# sym-var4.net
KiCad netlist of a schematic drawn in EAGLE
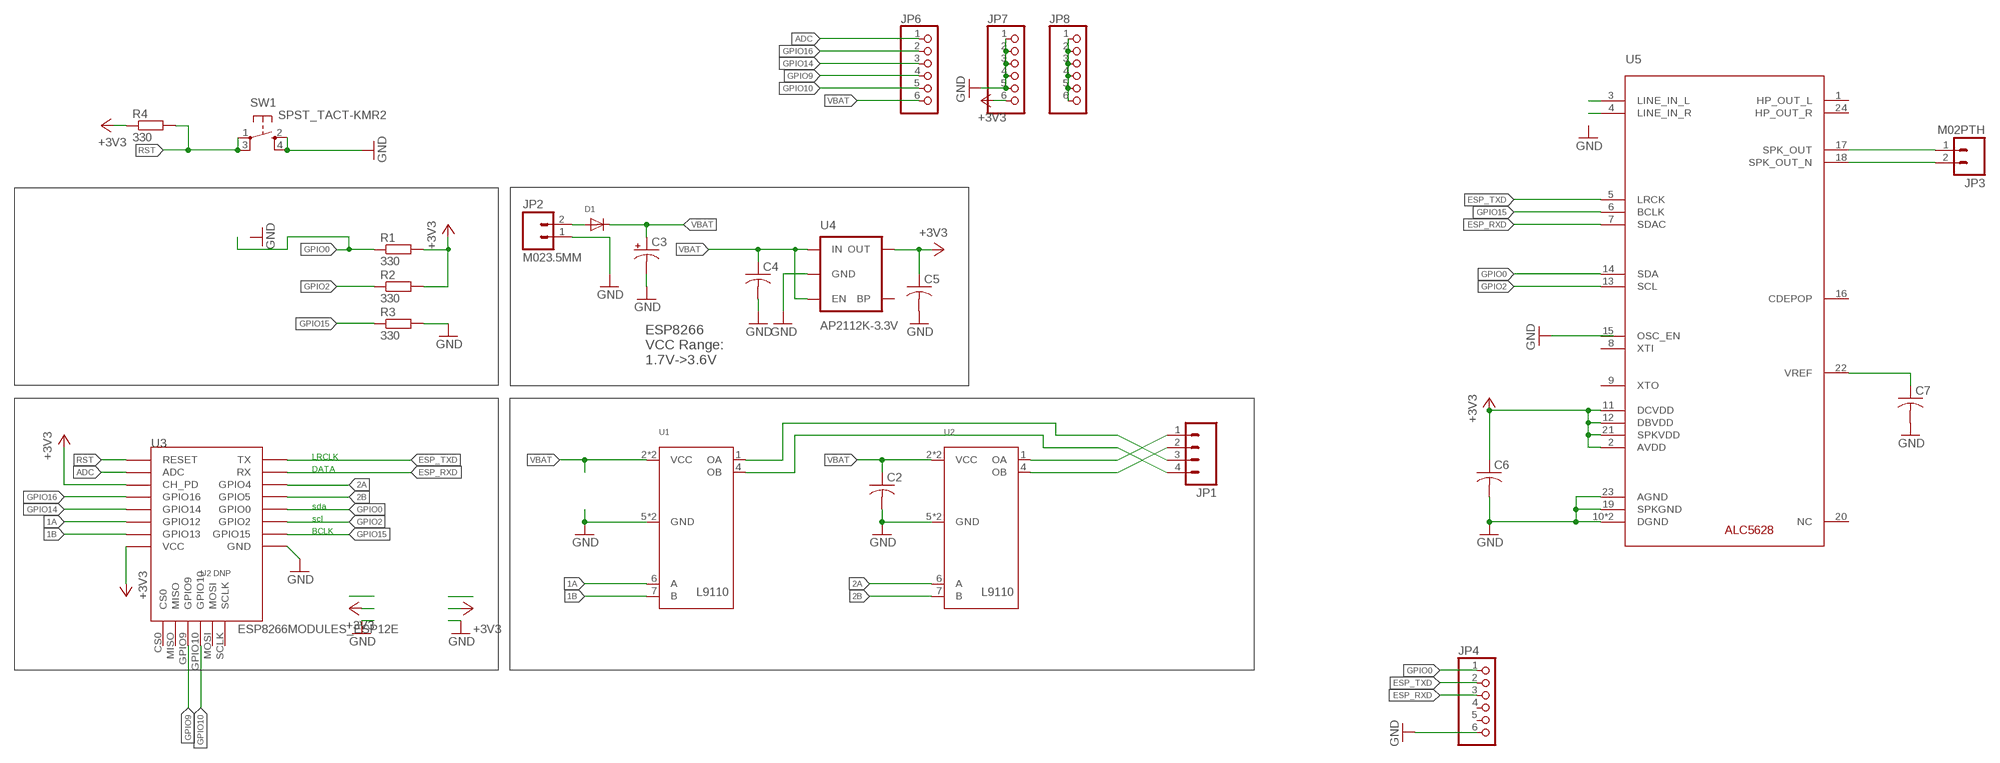
[diagram p0: schematic, sheet 1]

(export (version "E")
  (design (tool "Eeschema 10.0.6"))
  (components
    (comp (ref "C2")
      (value "C-USC0805")
      (footprint "eagle-import:C0805")
      (libsource (lib "eagle-import") (part "C-USC0805"))
    )
    (comp (ref "C3")
      (value "CPOL-USE2-5")
      (footprint "eagle-import:E2-5")
      (libsource (lib "eagle-import") (part "CPOL-USE2-5"))
    )
    (comp (ref "C4")
      (value "C-USC0805")
      (footprint "eagle-import:C0805")
      (libsource (lib "eagle-import") (part "C-USC0805"))
    )
    (comp (ref "C5")
      (value "C-USC0805")
      (footprint "eagle-import:C0805")
      (libsource (lib "eagle-import") (part "C-USC0805"))
    )
    (comp (ref "C6")
      (value "C-USC0805")
      (footprint "eagle-import:C0805")
      (libsource (lib "eagle-import") (part "C-USC0805"))
    )
    (comp (ref "C7")
      (value "C-USC0805")
      (footprint "eagle-import:C0805")
      (libsource (lib "eagle-import") (part "C-USC0805"))
    )
    (comp (ref "D1")
      (value "DIODESMA")
      (footprint "eagle-import:SMADIODE")
      (libsource (lib "eagle-import") (part "DIODESMA"))
    )
    (comp (ref "JP1")
      (value "M04SCREW")
      (footprint "eagle-import:SCREWTERMINAL-3.5MM-4")
      (libsource (lib "eagle-import") (part "M04SCREW"))
    )
    (comp (ref "JP2")
      (value "M023.5MM")
      (footprint "eagle-import:SCREWTERMINAL-3.5MM-2")
      (libsource (lib "eagle-import") (part "M023.5MM"))
    )
    (comp (ref "JP3")
      (value "M02PTH")
      (footprint "eagle-import:1X02")
      (libsource (lib "eagle-import") (part "M02PTH"))
    )
    (comp (ref "JP4")
      (value "PINHD-1X6")
      (footprint "eagle-import:1X06")
      (libsource (lib "eagle-import") (part "PINHD-1X6"))
    )
    (comp (ref "JP6")
      (value "PINHD-1X6")
      (footprint "eagle-import:1X06")
      (libsource (lib "eagle-import") (part "PINHD-1X6"))
    )
    (comp (ref "JP7")
      (value "PINHD-1X6")
      (footprint "eagle-import:1X06")
      (libsource (lib "eagle-import") (part "PINHD-1X6"))
    )
    (comp (ref "JP8")
      (value "PINHD-1X6")
      (footprint "eagle-import:1X06")
      (libsource (lib "eagle-import") (part "PINHD-1X6"))
    )
    (comp (ref "R1")
      (value "330")
      (footprint "eagle-import:R0805")
      (libsource (lib "eagle-import") (part "R-EU_R0805"))
    )
    (comp (ref "R2")
      (value "330")
      (footprint "eagle-import:R0805")
      (libsource (lib "eagle-import") (part "R-EU_R0805"))
    )
    (comp (ref "R3")
      (value "330")
      (footprint "eagle-import:R0805")
      (libsource (lib "eagle-import") (part "R-EU_R0805"))
    )
    (comp (ref "R4")
      (value "330")
      (footprint "eagle-import:R0805")
      (libsource (lib "eagle-import") (part "R-EU_R0805"))
    )
    (comp (ref "SW1")
      (value "SPST_TACT-KMR2")
      (footprint "eagle-import:KMR2")
      (libsource (lib "eagle-import") (part "SPST_TACT-KMR2"))
    )
    (comp (ref "U1")
      (value "L9110")
      (footprint "eagle-import:DIP8")
      (libsource (lib "eagle-import") (part "L9110"))
    )
    (comp (ref "U2")
      (value "L9110")
      (footprint "eagle-import:DIP8")
      (libsource (lib "eagle-import") (part "L9110"))
    )
    (comp (ref "U3")
      (value "ESP8266MODULES_ESP12E")
      (footprint "eagle-import:ESP8266MODULES_ESP12E")
      (libsource (lib "eagle-import") (part "ESP8266MODULES_ESP12E"))
    )
    (comp (ref "U4")
      (value "AP2112K-3.3V")
      (footprint "eagle-import:SOT23-5")
      (libsource (lib "eagle-import") (part "V_REG_LDOSMD"))
    )
    (comp (ref "U5")
      (value "ALC5628")
      (footprint "eagle-import:QFN24")
      (libsource (lib "eagle-import") (part "ALC5628"))
    )
  )
  (nets
    (net (code "1") (name "+3V3") (class "Default")
      (node (ref "C5") (pin "1") (pinfunction "1_1") (pintype "passive"))
      (node (ref "C6") (pin "1") (pinfunction "1_1") (pintype "passive"))
      (node (ref "JP7") (pin "6") (pinfunction "6_6") (pintype "passive"))
      (node (ref "R1") (pin "2") (pinfunction "2_2") (pintype "passive"))
      (node (ref "R2") (pin "2") (pinfunction "2_2") (pintype "passive"))
      (node (ref "R4") (pin "1") (pinfunction "1_1") (pintype "passive"))
      (node (ref "U3") (pin "CH_PD") (pinfunction "CH_PD_CH_PD") (pintype "bidirectional"))
      (node (ref "U3") (pin "VCC") (pinfunction "VCC_VCC") (pintype "bidirectional"))
      (node (ref "U4") (pin "5") (pinfunction "OUT_5") (pintype "passive"))
      (node (ref "U5") (pin "11") (pinfunction "DCVDD_11") (pintype "bidirectional"))
      (node (ref "U5") (pin "12") (pinfunction "DBVDD_12") (pintype "bidirectional"))
      (node (ref "U5") (pin "2") (pinfunction "AVDD_2") (pintype "bidirectional"))
      (node (ref "U5") (pin "21") (pinfunction "SPKVDD_21") (pintype "bidirectional"))
    )
    (net (code "2") (name "1A") (class "Default")
      (node (ref "U1") (pin "6") (pinfunction "A_6") (pintype "bidirectional"))
      (node (ref "U3") (pin "GPIO12") (pinfunction "GPIO12_GPIO12") (pintype "bidirectional"))
    )
    (net (code "3") (name "1B") (class "Default")
      (node (ref "U1") (pin "7") (pinfunction "B_7") (pintype "bidirectional"))
      (node (ref "U3") (pin "GPIO_13") (pinfunction "GPIO13_GPIO_13") (pintype "bidirectional"))
    )
    (net (code "4") (name "2A") (class "Default")
      (node (ref "U2") (pin "6") (pinfunction "A_6") (pintype "bidirectional"))
      (node (ref "U3") (pin "GPIO4") (pinfunction "GPIO4_GPIO4") (pintype "bidirectional"))
    )
    (net (code "5") (name "2B") (class "Default")
      (node (ref "U2") (pin "7") (pinfunction "B_7") (pintype "bidirectional"))
      (node (ref "U3") (pin "GPIO5") (pinfunction "GPIO5_GPIO5") (pintype "bidirectional"))
    )
    (net (code "6") (name "ADC") (class "Default")
      (node (ref "JP6") (pin "1") (pinfunction "1_1") (pintype "passive"))
      (node (ref "U3") (pin "ADC") (pinfunction "ADC_ADC") (pintype "bidirectional"))
    )
    (net (code "7") (name "ESP_RXD") (class "Default")
      (node (ref "JP4") (pin "3") (pinfunction "3_3") (pintype "passive"))
      (node (ref "U3") (pin "RX") (pinfunction "RX_RX") (pintype "bidirectional"))
      (node (ref "U5") (pin "7") (pinfunction "SDAC_7") (pintype "bidirectional"))
    )
    (net (code "8") (name "ESP_TXD") (class "Default")
      (node (ref "JP4") (pin "2") (pinfunction "2_2") (pintype "passive"))
      (node (ref "U3") (pin "TX") (pinfunction "TX_TX") (pintype "bidirectional"))
      (node (ref "U5") (pin "5") (pinfunction "LRCK_5") (pintype "bidirectional"))
    )
    (net (code "9") (name "GND") (class "Default")
      (node (ref "C2") (pin "2") (pinfunction "2_2") (pintype "passive"))
      (node (ref "C3") (pin "-") (pinfunction "-_-") (pintype "passive"))
      (node (ref "C4") (pin "2") (pinfunction "2_2") (pintype "passive"))
      (node (ref "C5") (pin "2") (pinfunction "2_2") (pintype "passive"))
      (node (ref "C6") (pin "2") (pinfunction "2_2") (pintype "passive"))
      (node (ref "C7") (pin "2") (pinfunction "2_2") (pintype "passive"))
      (node (ref "JP2") (pin "1") (pinfunction "1_1") (pintype "passive"))
      (node (ref "JP4") (pin "6") (pinfunction "6_6") (pintype "passive"))
      (node (ref "JP7") (pin "1") (pinfunction "1_1") (pintype "passive"))
      (node (ref "JP7") (pin "2") (pinfunction "2_2") (pintype "passive"))
      (node (ref "JP7") (pin "3") (pinfunction "3_3") (pintype "passive"))
      (node (ref "JP7") (pin "4") (pinfunction "4_4") (pintype "passive"))
      (node (ref "JP7") (pin "5") (pinfunction "5_5") (pintype "passive"))
      (node (ref "R3") (pin "2") (pinfunction "2_2") (pintype "passive"))
      (node (ref "SW1") (pin "2") (pinfunction "S_2") (pintype "passive"))
      (node (ref "SW1") (pin "4") (pinfunction "S1_4") (pintype "passive"))
      (node (ref "U1") (pin "5") (pinfunction "GND_5") (pintype "bidirectional"))
      (node (ref "U1") (pin "8") (pinfunction "GND_8") (pintype "bidirectional"))
      (node (ref "U2") (pin "5") (pinfunction "GND_5") (pintype "bidirectional"))
      (node (ref "U2") (pin "8") (pinfunction "GND_8") (pintype "bidirectional"))
      (node (ref "U3") (pin "GND") (pinfunction "GND_GND") (pintype "bidirectional"))
      (node (ref "U4") (pin "2") (pinfunction "GND_2") (pintype "input"))
      (node (ref "U5") (pin "10") (pinfunction "DGND_10") (pintype "bidirectional"))
      (node (ref "U5") (pin "19") (pinfunction "SPKGND_19") (pintype "bidirectional"))
      (node (ref "U5") (pin "23") (pinfunction "AGND_23") (pintype "bidirectional"))
      (node (ref "U5") (pin "PAD") (pinfunction "DGND_PAD") (pintype "bidirectional"))
    )
    (net (code "10") (name "GPIO0") (class "Default")
      (node (ref "JP4") (pin "1") (pinfunction "1_1") (pintype "passive"))
      (node (ref "R1") (pin "1") (pinfunction "1_1") (pintype "passive"))
      (node (ref "U3") (pin "GPIO0") (pinfunction "GPIO0_GPIO0") (pintype "bidirectional"))
      (node (ref "U5") (pin "14") (pinfunction "SDA_14") (pintype "bidirectional"))
    )
    (net (code "11") (name "GPIO2") (class "Default")
      (node (ref "R2") (pin "1") (pinfunction "1_1") (pintype "passive"))
      (node (ref "U3") (pin "GPIO2") (pinfunction "GPIO2_GPIO2") (pintype "bidirectional"))
      (node (ref "U5") (pin "13") (pinfunction "SCL_13") (pintype "bidirectional"))
    )
    (net (code "12") (name "GPIO9") (class "Default")
      (node (ref "JP6") (pin "4") (pinfunction "4_4") (pintype "passive"))
      (node (ref "U3") (pin "GPIO9") (pinfunction "GPIO9_GPIO9") (pintype "bidirectional"))
    )
    (net (code "13") (name "GPIO10") (class "Default")
      (node (ref "JP6") (pin "5") (pinfunction "5_5") (pintype "passive"))
      (node (ref "U3") (pin "GPIO10") (pinfunction "GPIO10_GPIO10") (pintype "bidirectional"))
    )
    (net (code "14") (name "GPIO14") (class "Default")
      (node (ref "JP6") (pin "3") (pinfunction "3_3") (pintype "passive"))
      (node (ref "U3") (pin "GPIO14") (pinfunction "GPIO14_GPIO14") (pintype "bidirectional"))
    )
    (net (code "15") (name "GPIO15") (class "Default")
      (node (ref "R3") (pin "1") (pinfunction "1_1") (pintype "passive"))
      (node (ref "U3") (pin "GPIO15") (pinfunction "GPIO15_GPIO15") (pintype "bidirectional"))
      (node (ref "U5") (pin "6") (pinfunction "BCLK_6") (pintype "bidirectional"))
    )
    (net (code "16") (name "GPIO16") (class "Default")
      (node (ref "JP6") (pin "2") (pinfunction "2_2") (pintype "passive"))
      (node (ref "U3") (pin "GPIO_16") (pinfunction "GPIO16_GPIO_16") (pintype "bidirectional"))
    )
    (net (code "17") (name "Net-(D1-PadA)") (class "Default")
      (node (ref "D1") (pin "A") (pinfunction "A_A") (pintype "passive"))
      (node (ref "JP2") (pin "2") (pinfunction "2_2") (pintype "passive"))
    )
    (net (code "18") (name "Net-(JP8-Pad1)") (class "Default")
      (node (ref "JP8") (pin "1") (pinfunction "1_1") (pintype "passive"))
      (node (ref "JP8") (pin "2") (pinfunction "2_2") (pintype "passive"))
      (node (ref "JP8") (pin "3") (pinfunction "3_3") (pintype "passive"))
      (node (ref "JP8") (pin "4") (pinfunction "4_4") (pintype "passive"))
      (node (ref "JP8") (pin "5") (pinfunction "5_5") (pintype "passive"))
      (node (ref "JP8") (pin "6") (pinfunction "6_6") (pintype "passive"))
    )
    (net (code "19") (name "Net-(U1-OA)") (class "Default")
      (node (ref "JP1") (pin "3") (pinfunction "3_3") (pintype "passive"))
      (node (ref "U1") (pin "1") (pinfunction "OA_1") (pintype "bidirectional"))
    )
    (net (code "20") (name "Net-(U1-OB)") (class "Default")
      (node (ref "JP1") (pin "4") (pinfunction "4_4") (pintype "passive"))
      (node (ref "U1") (pin "4") (pinfunction "OB_4") (pintype "bidirectional"))
    )
    (net (code "21") (name "Net-(U2-OA)") (class "Default")
      (node (ref "JP1") (pin "1") (pinfunction "1_1") (pintype "passive"))
      (node (ref "U2") (pin "1") (pinfunction "OA_1") (pintype "bidirectional"))
    )
    (net (code "22") (name "Net-(U2-OB)") (class "Default")
      (node (ref "JP1") (pin "2") (pinfunction "2_2") (pintype "passive"))
      (node (ref "U2") (pin "4") (pinfunction "OB_4") (pintype "bidirectional"))
    )
    (net (code "23") (name "Net-(U5-SPK_OUT)") (class "Default")
      (node (ref "JP3") (pin "1") (pinfunction "1_1") (pintype "passive"))
      (node (ref "U5") (pin "17") (pinfunction "SPK_OUT_17") (pintype "bidirectional"))
    )
    (net (code "24") (name "Net-(U5-SPK_OUT_N)") (class "Default")
      (node (ref "JP3") (pin "2") (pinfunction "2_2") (pintype "passive"))
      (node (ref "U5") (pin "18") (pinfunction "SPK_OUT_N_18") (pintype "bidirectional"))
    )
    (net (code "25") (name "Net-(U5-VREF)") (class "Default")
      (node (ref "C7") (pin "1") (pinfunction "1_1") (pintype "passive"))
      (node (ref "U5") (pin "22") (pinfunction "VREF_22") (pintype "bidirectional"))
    )
    (net (code "26") (name "RST") (class "Default")
      (node (ref "R4") (pin "2") (pinfunction "2_2") (pintype "passive"))
      (node (ref "SW1") (pin "1") (pinfunction "P_1") (pintype "passive"))
      (node (ref "SW1") (pin "3") (pinfunction "P1_3") (pintype "passive"))
      (node (ref "U3") (pin "RESET") (pinfunction "RESET_RESET") (pintype "bidirectional"))
    )
    (net (code "27") (name "VBAT") (class "Default")
      (node (ref "C2") (pin "1") (pinfunction "1_1") (pintype "passive"))
      (node (ref "C3") (pin "+") (pinfunction "+_+") (pintype "passive"))
      (node (ref "C4") (pin "1") (pinfunction "1_1") (pintype "passive"))
      (node (ref "D1") (pin "C") (pinfunction "C_C") (pintype "passive"))
      (node (ref "JP6") (pin "6") (pinfunction "6_6") (pintype "passive"))
      (node (ref "U1") (pin "2") (pinfunction "VCC_2") (pintype "bidirectional"))
      (node (ref "U1") (pin "3") (pinfunction "VCC_3") (pintype "bidirectional"))
      (node (ref "U2") (pin "2") (pinfunction "VCC_2") (pintype "bidirectional"))
      (node (ref "U2") (pin "3") (pinfunction "VCC_3") (pintype "bidirectional"))
      (node (ref "U4") (pin "1") (pinfunction "IN_1") (pintype "input"))
      (node (ref "U4") (pin "3") (pinfunction "EN_3") (pintype "input"))
    )
    (net (code "28") (name "unconnected-(JP4-Pad4)") (class "Default")
      (node (ref "JP4") (pin "4") (pinfunction "4_4") (pintype "passive"))
    )
    (net (code "29") (name "unconnected-(JP4-Pad5)") (class "Default")
      (node (ref "JP4") (pin "5") (pinfunction "5_5") (pintype "passive"))
    )
    (net (code "30") (name "unconnected-(U3-PadCS0)") (class "Default")
      (node (ref "U3") (pin "CS0") (pinfunction "CS0_CS0") (pintype "bidirectional"))
    )
    (net (code "31") (name "unconnected-(U3-PadMISO)") (class "Default")
      (node (ref "U3") (pin "MISO") (pinfunction "MISO_MISO") (pintype "bidirectional"))
    )
    (net (code "32") (name "unconnected-(U3-PadMOSI)") (class "Default")
      (node (ref "U3") (pin "MOSI") (pinfunction "MOSI_MOSI") (pintype "bidirectional"))
    )
    (net (code "33") (name "unconnected-(U3-PadSCLK)") (class "Default")
      (node (ref "U3") (pin "SCLK") (pinfunction "SCLK_SCLK") (pintype "bidirectional"))
    )
    (net (code "34") (name "unconnected-(U4-BP-Pad4)") (class "Default")
      (node (ref "U4") (pin "4") (pinfunction "BP_4") (pintype "input"))
    )
    (net (code "35") (name "unconnected-(U5-CDEPOP-Pad16)") (class "Default")
      (node (ref "U5") (pin "16") (pinfunction "CDEPOP_16") (pintype "bidirectional"))
    )
    (net (code "36") (name "unconnected-(U5-HP_OUT_L-Pad1)") (class "Default")
      (node (ref "U5") (pin "1") (pinfunction "HP_OUT_L_1") (pintype "bidirectional"))
    )
    (net (code "37") (name "unconnected-(U5-HP_OUT_R-Pad24)") (class "Default")
      (node (ref "U5") (pin "24") (pinfunction "HP_OUT_R_24") (pintype "bidirectional"))
    )
    (net (code "38") (name "unconnected-(U5-LINE_IN_L-Pad3)") (class "Default")
      (node (ref "U5") (pin "3") (pinfunction "LINE_IN_L_3") (pintype "bidirectional"))
    )
    (net (code "39") (name "unconnected-(U5-LINE_IN_R-Pad4)") (class "Default")
      (node (ref "U5") (pin "4") (pinfunction "LINE_IN_R_4") (pintype "bidirectional"))
    )
    (net (code "40") (name "unconnected-(U5-NC-Pad20)") (class "Default")
      (node (ref "U5") (pin "20") (pinfunction "NC_20") (pintype "bidirectional"))
    )
    (net (code "41") (name "unconnected-(U5-OSC_EN-Pad15)") (class "Default")
      (node (ref "U5") (pin "15") (pinfunction "OSC_EN_15") (pintype "bidirectional"))
    )
    (net (code "42") (name "unconnected-(U5-XTI-Pad8)") (class "Default")
      (node (ref "U5") (pin "8") (pinfunction "XTI_8") (pintype "bidirectional"))
    )
    (net (code "43") (name "unconnected-(U5-XTO-Pad9)") (class "Default")
      (node (ref "U5") (pin "9") (pinfunction "XTO_9") (pintype "bidirectional"))
    )
  )
)
